# Aruduino-Kids-Shiled.net
KiCad netlist of a schematic drawn in EAGLE
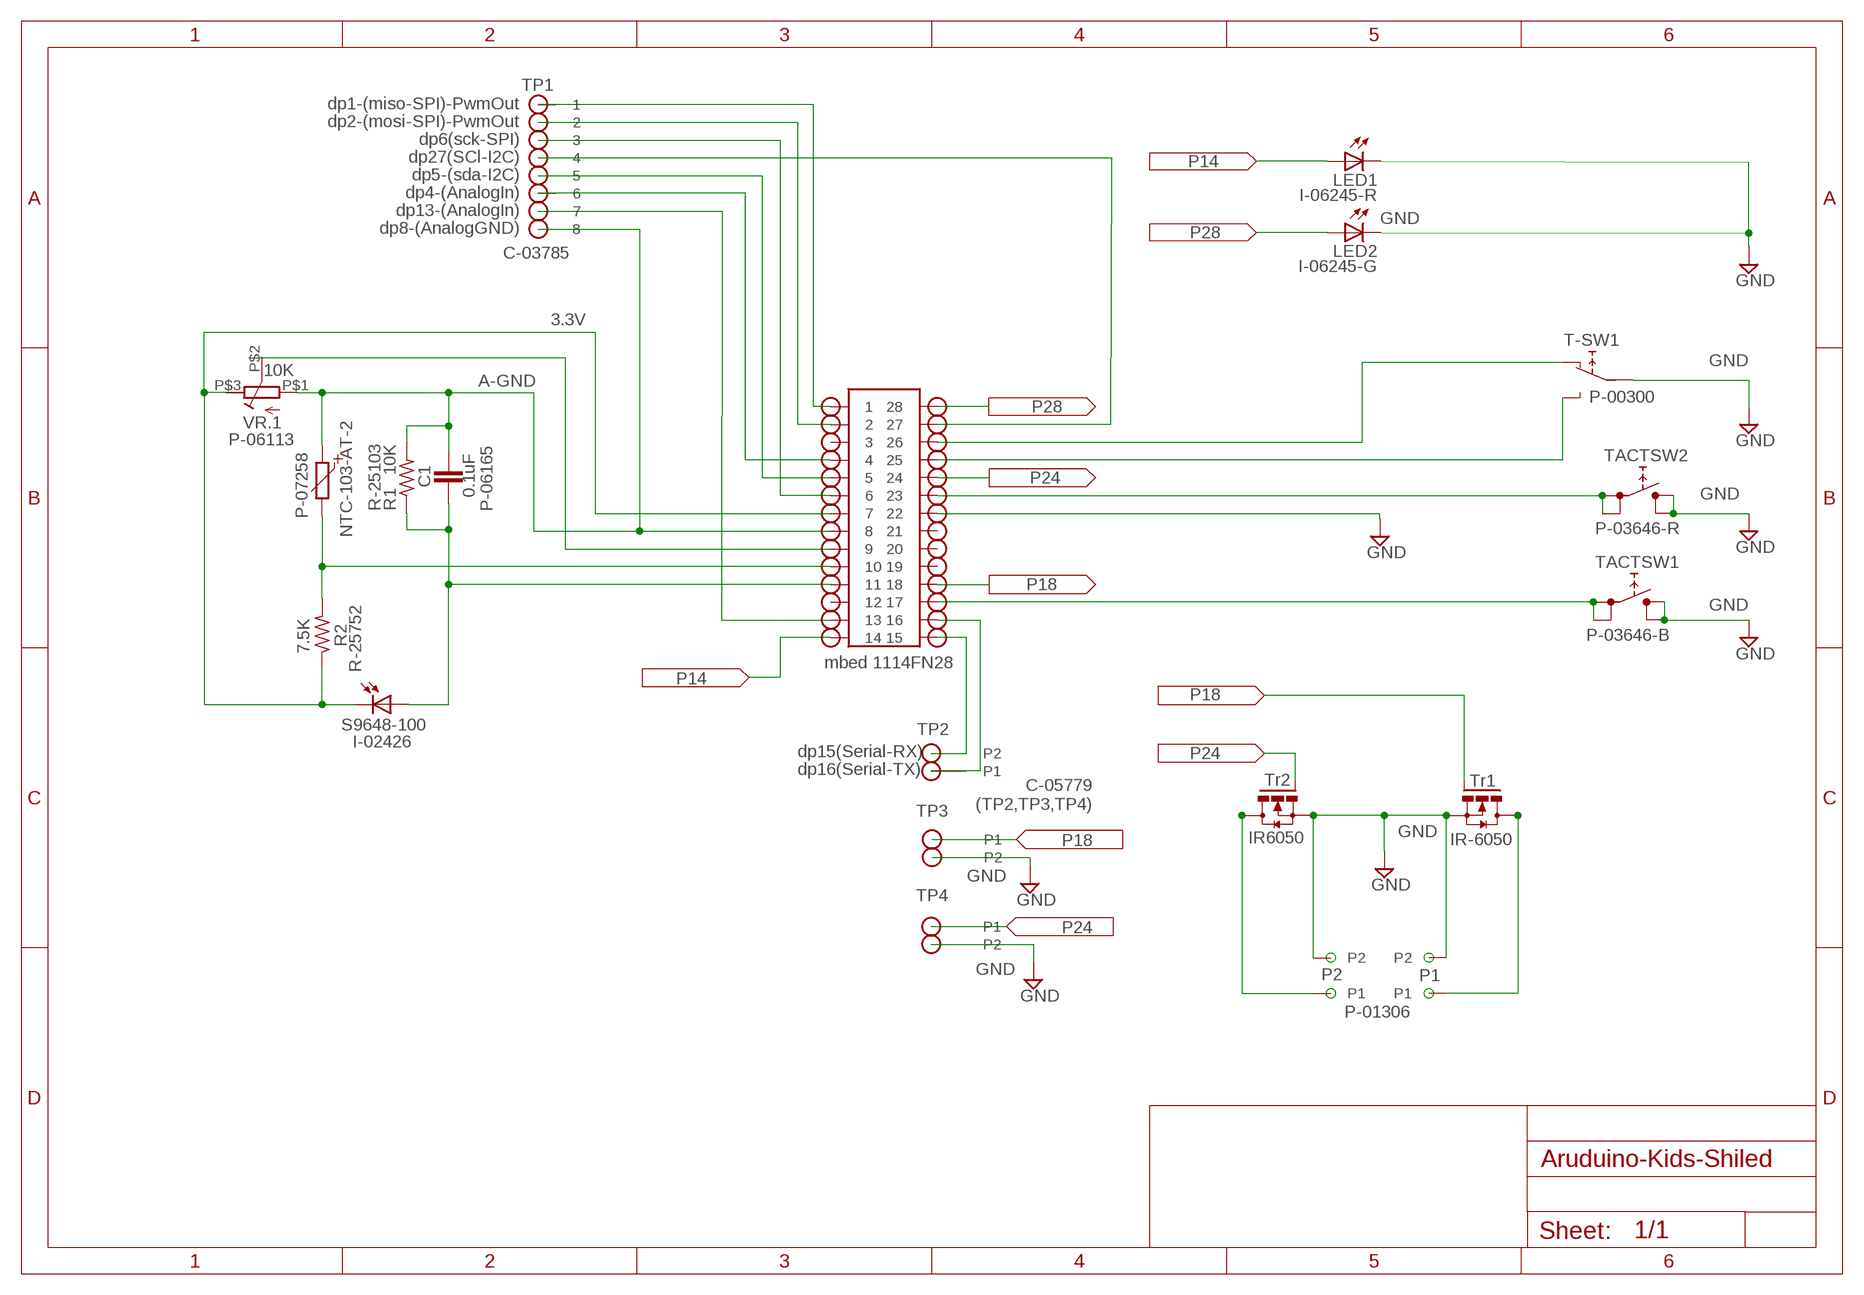
[diagram p0: schematic, sheet 1]

(export (version "E")
  (design (tool "Eeschema 10.0.6"))
  (components
    (comp (ref "0-50C")
      (value "NTC-103-AT-2")
      (footprint "eagle-import:NTC")
      (libsource (lib "eagle-import") (part "NTC-103-AT-2"))
    )
    (comp (ref "C1")
      (value "0.1uF")
      (footprint "eagle-import:C")
      (libsource (lib "eagle-import") (part "C-RPEF"))
    )
    (comp (ref "LED1")
      (value "I-06245-R")
      (footprint "eagle-import:LED5MM")
      (libsource (lib "eagle-import") (part "LED5MM"))
    )
    (comp (ref "LED2")
      (value "I-06245-G")
      (footprint "eagle-import:LED5MM")
      (libsource (lib "eagle-import") (part "LED5MM"))
    )
    (comp (ref "R1")
      (value "10K")
      (footprint "eagle-import:R12MM")
      (libsource (lib "eagle-import") (part "R"))
    )
    (comp (ref "R2")
      (value "7.5K")
      (footprint "eagle-import:R12MM")
      (libsource (lib "eagle-import") (part "R"))
    )
    (comp (ref "T-SW1")
      (value "P-00300")
      (footprint "eagle-import:TOGLE-SW")
      (libsource (lib "eagle-import") (part "SW-2MS1-T1-B4-VS2-Q-E-TOGLE"))
    )
    (comp (ref "TACTSW1")
      (value "P-03646-B")
      (footprint "eagle-import:TACT-SW")
      (libsource (lib "eagle-import") (part "TACT-SW"))
    )
    (comp (ref "TACTSW2")
      (value "P-03646-R")
      (footprint "eagle-import:TACT-SW")
      (libsource (lib "eagle-import") (part "TACT-SW"))
    )
    (comp (ref "TB1")
      (value "P-01306")
      (footprint "eagle-import:TB")
      (libsource (lib "eagle-import") (part "TB112-2-2-U-1"))
    )
    (comp (ref "TB2")
      (value "P-01306")
      (footprint "eagle-import:TB")
      (libsource (lib "eagle-import") (part "TB112-2-2-U-1"))
    )
    (comp (ref "U$1")
      (value "FH-1X14")
      (footprint "eagle-import:DIP28-SOCKET")
      (libsource (lib "eagle-import") (part "FH-1X14"))
    )
    (comp (ref "U$2")
      (value "S9648-100")
      (footprint "eagle-import:PHOTO-IC")
      (libsource (lib "eagle-import") (part "S9648-100"))
    )
    (comp (ref "U$3")
      (value "SIPS-7")
      (footprint "eagle-import:SIPC-7")
      (libsource (lib "eagle-import") (part "SIPS-7"))
    )
    (comp (ref "U$4")
      (value "IR-6050")
      (footprint "eagle-import:TO251AA")
      (libsource (lib "eagle-import") (part "ＩＲＦＵ１２０Ｎ"))
    )
    (comp (ref "U$5")
      (value "IR6050")
      (footprint "eagle-import:TO251AA")
      (libsource (lib "eagle-import") (part "ＩＲＦＵ１２０Ｎ"))
    )
    (comp (ref "U$6")
      (value "SIPS-2")
      (footprint "eagle-import:SIPC-2")
      (libsource (lib "eagle-import") (part "SIPS-2"))
    )
    (comp (ref "U$9")
      (value "SIPS-2")
      (footprint "eagle-import:SIPC-2")
      (libsource (lib "eagle-import") (part "SIPS-2"))
    )
    (comp (ref "U$10")
      (value "SIPS-2")
      (footprint "eagle-import:SIPC-2")
      (libsource (lib "eagle-import") (part "SIPS-2"))
    )
    (comp (ref "VR.1")
      (value "10K")
      (footprint "eagle-import:VOL-TRIM")
      (libsource (lib "eagle-import") (part "TSR-3386K"))
    )
  )
  (nets
    (net (code "1") (name "/3.3V") (class "Default")
      (node (ref "R2") (pin "1") (pinfunction "1_1") (pintype "passive"))
      (node (ref "U$1") (pin "P$7") (pinfunction "7_P$7") (pintype "bidirectional"))
      (node (ref "U$2") (pin "P$2") (pinfunction "C_P$2") (pintype "passive"))
      (node (ref "VR.1") (pin "P$3") (pinfunction "E_P$3") (pintype "passive"))
    )
    (net (code "2") (name "/A-GND") (class "Default")
      (node (ref "0-50C") (pin "1") (pinfunction "1_1") (pintype "passive"))
      (node (ref "C1") (pin "1") (pinfunction "1_1") (pintype "passive"))
      (node (ref "R1") (pin "2") (pinfunction "2_2") (pintype "passive"))
      (node (ref "U$1") (pin "P$8") (pinfunction "8_P$8") (pintype "bidirectional"))
      (node (ref "U$3") (pin "P$8") (pinfunction "8_P$8") (pintype "passive"))
      (node (ref "VR.1") (pin "P$1") (pinfunction "A_P$1") (pintype "passive"))
    )
    (net (code "3") (name "/P14") (class "Default")
      (node (ref "LED1") (pin "A") (pinfunction "A_A") (pintype "passive"))
      (node (ref "U$1") (pin "P$14") (pinfunction "14_P$14") (pintype "bidirectional"))
    )
    (net (code "4") (name "/P18") (class "Default")
      (node (ref "U$1") (pin "P$18") (pinfunction "18_P$18") (pintype "bidirectional"))
      (node (ref "U$10") (pin "P$1") (pinfunction "P1_P$1") (pintype "bidirectional"))
      (node (ref "U$4") (pin "1") (pinfunction "G_1") (pintype "passive"))
    )
    (net (code "5") (name "/P24") (class "Default")
      (node (ref "U$1") (pin "P$24") (pinfunction "24_P$24") (pintype "bidirectional"))
      (node (ref "U$5") (pin "1") (pinfunction "G_1") (pintype "passive"))
      (node (ref "U$9") (pin "P$1") (pinfunction "P1_P$1") (pintype "bidirectional"))
    )
    (net (code "6") (name "/P28") (class "Default")
      (node (ref "LED2") (pin "A") (pinfunction "A_A") (pintype "passive"))
      (node (ref "U$1") (pin "P$28") (pinfunction "28_P$28") (pintype "bidirectional"))
    )
    (net (code "7") (name "GND") (class "Default")
      (node (ref "LED1") (pin "K") (pinfunction "C_K") (pintype "passive"))
      (node (ref "LED2") (pin "K") (pinfunction "C_K") (pintype "passive"))
      (node (ref "T-SW1") (pin "P$2") (pinfunction "2COM_P$2") (pintype "passive"))
      (node (ref "TACTSW1") (pin "1") (pinfunction "4_1") (pintype "passive"))
      (node (ref "TACTSW1") (pin "2") (pinfunction "2_2") (pintype "passive"))
      (node (ref "TACTSW2") (pin "1") (pinfunction "4_1") (pintype "passive"))
      (node (ref "TACTSW2") (pin "2") (pinfunction "2_2") (pintype "passive"))
      (node (ref "TB1") (pin "P$2") (pinfunction "P2_P$2") (pintype "passive"))
      (node (ref "TB2") (pin "P$2") (pinfunction "P2_P$2") (pintype "passive"))
      (node (ref "U$1") (pin "P$22") (pinfunction "22_P$22") (pintype "bidirectional"))
      (node (ref "U$10") (pin "P$2") (pinfunction "P2_P$2") (pintype "bidirectional"))
      (node (ref "U$4") (pin "3") (pinfunction "S_3") (pintype "passive"))
      (node (ref "U$5") (pin "3") (pinfunction "S_3") (pintype "passive"))
      (node (ref "U$9") (pin "P$2") (pinfunction "P2_P$2") (pintype "bidirectional"))
    )
    (net (code "8") (name "Net-(T-SW1-1)") (class "Default")
      (node (ref "T-SW1") (pin "P$1") (pinfunction "1_P$1") (pintype "passive"))
      (node (ref "U$1") (pin "P$26") (pinfunction "26_P$26") (pintype "bidirectional"))
    )
    (net (code "9") (name "Net-(T-SW1-3)") (class "Default")
      (node (ref "T-SW1") (pin "P$3") (pinfunction "3_P$3") (pintype "passive"))
      (node (ref "U$1") (pin "P$25") (pinfunction "25_P$25") (pintype "bidirectional"))
    )
    (net (code "10") (name "Net-(TACTSW1-1)") (class "Default")
      (node (ref "TACTSW1") (pin "3") (pinfunction "3_3") (pintype "passive"))
      (node (ref "TACTSW1") (pin "4") (pinfunction "1_4") (pintype "passive"))
      (node (ref "U$1") (pin "P$17") (pinfunction "17_P$17") (pintype "bidirectional"))
    )
    (net (code "11") (name "Net-(TACTSW2-1)") (class "Default")
      (node (ref "TACTSW2") (pin "3") (pinfunction "3_3") (pintype "passive"))
      (node (ref "TACTSW2") (pin "4") (pinfunction "1_4") (pintype "passive"))
      (node (ref "U$1") (pin "P$23") (pinfunction "23_P$23") (pintype "bidirectional"))
    )
    (net (code "12") (name "Net-(TB1-P1)") (class "Default")
      (node (ref "TB1") (pin "P$1") (pinfunction "P1_P$1") (pintype "passive"))
      (node (ref "U$4") (pin "2") (pinfunction "D_2") (pintype "passive"))
      (node (ref "U$4") (pin "4") (pinfunction "D_4") (pintype "passive"))
    )
    (net (code "13") (name "Net-(TB2-P1)") (class "Default")
      (node (ref "TB2") (pin "P$1") (pinfunction "P1_P$1") (pintype "passive"))
      (node (ref "U$5") (pin "2") (pinfunction "D_2") (pintype "passive"))
      (node (ref "U$5") (pin "4") (pinfunction "D_4") (pintype "passive"))
    )
    (net (code "14") (name "Net-(U$1-1)") (class "Default")
      (node (ref "U$1") (pin "P$1") (pinfunction "1_P$1") (pintype "bidirectional"))
      (node (ref "U$3") (pin "P$1") (pinfunction "1_P$1") (pintype "passive"))
    )
    (net (code "15") (name "Net-(U$1-2)") (class "Default")
      (node (ref "U$1") (pin "P$2") (pinfunction "2_P$2") (pintype "bidirectional"))
      (node (ref "U$3") (pin "P$2") (pinfunction "2_P$2") (pintype "passive"))
    )
    (net (code "16") (name "Net-(U$1-4)") (class "Default")
      (node (ref "U$1") (pin "P$4") (pinfunction "4_P$4") (pintype "bidirectional"))
      (node (ref "U$3") (pin "P$6") (pinfunction "6_P$6") (pintype "passive"))
    )
    (net (code "17") (name "Net-(U$1-5)") (class "Default")
      (node (ref "U$1") (pin "P$5") (pinfunction "5_P$5") (pintype "bidirectional"))
      (node (ref "U$3") (pin "P$5") (pinfunction "5_P$5") (pintype "passive"))
    )
    (net (code "18") (name "Net-(U$1-6)") (class "Default")
      (node (ref "U$1") (pin "P$6") (pinfunction "6_P$6") (pintype "bidirectional"))
      (node (ref "U$3") (pin "P$3") (pinfunction "3_P$3") (pintype "passive"))
    )
    (net (code "19") (name "Net-(U$1-9)") (class "Default")
      (node (ref "U$1") (pin "P$9") (pinfunction "9_P$9") (pintype "bidirectional"))
      (node (ref "VR.1") (pin "P$2") (pinfunction "S_P$2") (pintype "passive"))
    )
    (net (code "20") (name "Net-(U$1-10)") (class "Default")
      (node (ref "0-50C") (pin "2") (pinfunction "2_2") (pintype "passive"))
      (node (ref "R2") (pin "2") (pinfunction "2_2") (pintype "passive"))
      (node (ref "U$1") (pin "P$10") (pinfunction "10_P$10") (pintype "bidirectional"))
    )
    (net (code "21") (name "Net-(U$1-11)") (class "Default")
      (node (ref "C1") (pin "2") (pinfunction "2_2") (pintype "passive"))
      (node (ref "R1") (pin "1") (pinfunction "1_1") (pintype "passive"))
      (node (ref "U$1") (pin "P$11") (pinfunction "11_P$11") (pintype "bidirectional"))
      (node (ref "U$2") (pin "P$1") (pinfunction "A_P$1") (pintype "passive"))
    )
    (net (code "22") (name "Net-(U$1-13)") (class "Default")
      (node (ref "U$1") (pin "P$13") (pinfunction "13_P$13") (pintype "bidirectional"))
      (node (ref "U$3") (pin "P$7") (pinfunction "7_P$7") (pintype "passive"))
    )
    (net (code "23") (name "Net-(U$1-15)") (class "Default")
      (node (ref "U$1") (pin "P$15") (pinfunction "15_P$15") (pintype "bidirectional"))
      (node (ref "U$6") (pin "P$2") (pinfunction "P2_P$2") (pintype "bidirectional"))
    )
    (net (code "24") (name "Net-(U$1-16)") (class "Default")
      (node (ref "U$1") (pin "P$16") (pinfunction "16_P$16") (pintype "bidirectional"))
      (node (ref "U$6") (pin "P$1") (pinfunction "P1_P$1") (pintype "bidirectional"))
    )
    (net (code "25") (name "Net-(U$1-27)") (class "Default")
      (node (ref "U$1") (pin "P$27") (pinfunction "27_P$27") (pintype "bidirectional"))
      (node (ref "U$3") (pin "P$4") (pinfunction "4_P$4") (pintype "passive"))
    )
    (net (code "26") (name "unconnected-(U$1-3-PadP$3)") (class "Default")
      (node (ref "U$1") (pin "P$3") (pinfunction "3_P$3") (pintype "bidirectional"))
    )
    (net (code "27") (name "unconnected-(U$1-12-PadP$12)") (class "Default")
      (node (ref "U$1") (pin "P$12") (pinfunction "12_P$12") (pintype "bidirectional"))
    )
    (net (code "28") (name "unconnected-(U$1-19-PadP$19)") (class "Default")
      (node (ref "U$1") (pin "P$19") (pinfunction "19_P$19") (pintype "bidirectional"))
    )
    (net (code "29") (name "unconnected-(U$1-20-PadP$20)") (class "Default")
      (node (ref "U$1") (pin "P$20") (pinfunction "20_P$20") (pintype "bidirectional"))
    )
    (net (code "30") (name "unconnected-(U$1-21-PadP$21)") (class "Default")
      (node (ref "U$1") (pin "P$21") (pinfunction "21_P$21") (pintype "bidirectional"))
    )
  )
)
